# rgbstripe_msgeq7.net
KiCad netlist of a schematic drawn in EAGLE
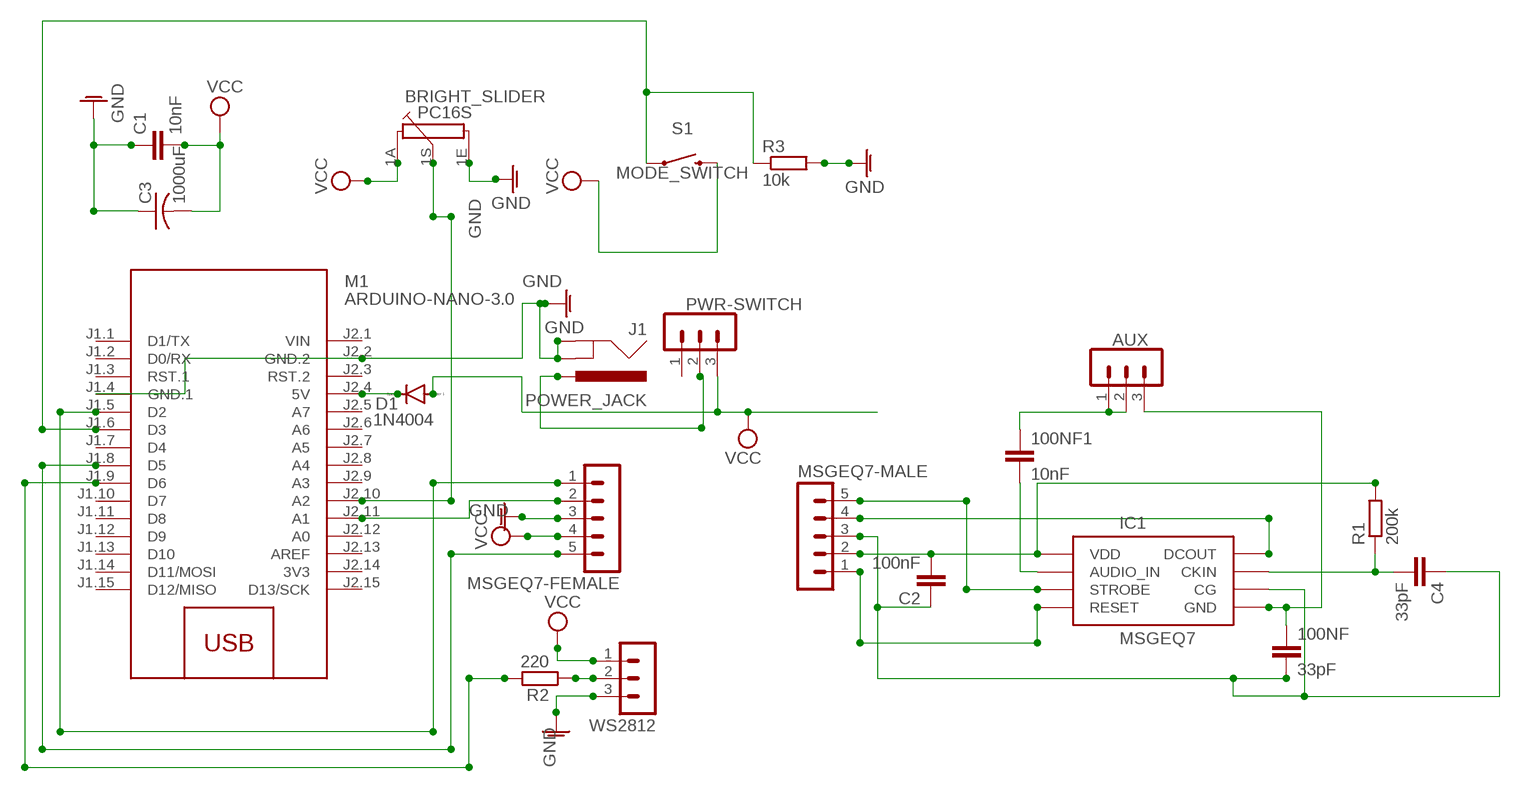
[diagram p0: schematic, sheet 1]

(export (version "E")
  (design (tool "Eeschema 10.0.6"))
  (components
    (comp (ref "100NF")
      (value "33pF")
      (footprint "eagle-import:C025-025X050")
      (libsource (lib "eagle-import") (part "C-EU025-025X050"))
    )
    (comp (ref "100NF1")
      (value "10nF")
      (footprint "eagle-import:C025-025X050")
      (libsource (lib "eagle-import") (part "C-EU025-025X050"))
    )
    (comp (ref "AUX")
      (value "MA03-1")
      (footprint "eagle-import:MA03-1")
      (libsource (lib "eagle-import") (part "MA03-1"))
    )
    (comp (ref "BRIGHT_SLIDER")
      (value "PC16S")
      (footprint "eagle-import:PC16S")
      (libsource (lib "eagle-import") (part "PC16S"))
    )
    (comp (ref "C1")
      (value "10nF")
      (footprint "eagle-import:C025-025X050")
      (libsource (lib "eagle-import") (part "C-EU025-025X050"))
    )
    (comp (ref "C2")
      (value "100nF")
      (footprint "eagle-import:C025-025X050")
      (libsource (lib "eagle-import") (part "C-EU025-025X050"))
    )
    (comp (ref "C3")
      (value "1000uF")
      (footprint "eagle-import:C050-024X044")
      (libsource (lib "eagle-import") (part "C-US050-024X044"))
    )
    (comp (ref "C4")
      (value "33pF")
      (footprint "eagle-import:C025-025X050")
      (libsource (lib "eagle-import") (part "C-EU025-025X050"))
    )
    (comp (ref "D1")
      (value "1N4004")
      (footprint "eagle-import:DO41-10")
      (libsource (lib "eagle-import") (part "1N4004"))
    )
    (comp (ref "IC1")
      (value "MSGEQ7P")
      (footprint "eagle-import:DIP08")
      (libsource (lib "eagle-import") (part "MSGEQ7DIL"))
    )
    (comp (ref "J1")
      (value "POWER_JACK")
      (footprint "eagle-import:POWER_JACK_PTH")
      (libsource (lib "eagle-import") (part "POWER_JACK"))
    )
    (comp (ref "M1")
      (value "ARDUINO-NANO-3.0")
      (footprint "eagle-import:ARDUINO-NANO-3.0")
      (libsource (lib "eagle-import") (part "ARDUINO-NANO-3.0"))
    )
    (comp (ref "MSGEQ7-FEMALE")
      (value "MA05-1")
      (footprint "eagle-import:MA05-1")
      (libsource (lib "eagle-import") (part "MA05-1"))
    )
    (comp (ref "MSGEQ7-MALE")
      (value "MA05-1")
      (footprint "eagle-import:MA05-1")
      (libsource (lib "eagle-import") (part "MA05-1"))
    )
    (comp (ref "PWR-SWITCH")
      (value "MA03-1")
      (footprint "eagle-import:MA03-1")
      (libsource (lib "eagle-import") (part "MA03-1"))
    )
    (comp (ref "R1")
      (value "200k")
      (footprint "eagle-import:0204_5")
      (libsource (lib "eagle-import") (part "R-EU_0204/5"))
    )
    (comp (ref "R2")
      (value "220")
      (footprint "eagle-import:0204_5")
      (libsource (lib "eagle-import") (part "R-EU_0204/5"))
    )
    (comp (ref "R3")
      (value "10k")
      (footprint "eagle-import:0204_5")
      (libsource (lib "eagle-import") (part "R-EU_0204/5"))
    )
    (comp (ref "S1")
      (value "MODE_SWITCH")
      (footprint "eagle-import:TACTILE_SWITCH_PTH_12MM")
      (libsource (lib "eagle-import") (part "MOMENTARY-SWITCH-SPST-PTH-12MM"))
    )
    (comp (ref "WS2812")
      (value "MA03-1")
      (footprint "eagle-import:MA03-1")
      (libsource (lib "eagle-import") (part "MA03-1"))
    )
  )
  (nets
    (net (code "1") (name "/3V3") (class "Default")
      (node (ref "M1") (pin "J2.14") (pinfunction "3V3_J2.14") (pintype "power_in"))
    )
    (net (code "2") (name "/VIN") (class "Default")
      (node (ref "M1") (pin "J2.1") (pinfunction "VIN_J2.1") (pintype "power_in"))
    )
    (net (code "3") (name "GND") (class "Default")
      (node (ref "BRIGHT_SLIDER") (pin "1E") (pinfunction "1E_1E") (pintype "passive"))
      (node (ref "C1") (pin "1") (pinfunction "1_1") (pintype "passive"))
      (node (ref "C3") (pin "1") (pinfunction "1_1") (pintype "passive"))
      (node (ref "J1") (pin "GND") (pinfunction "GND_GND") (pintype "bidirectional"))
      (node (ref "J1") (pin "GNDBREAK") (pinfunction "GNDBREAK_GNDBREAK") (pintype "bidirectional"))
      (node (ref "M1") (pin "J1.4") (pinfunction "GND.1_J1.4") (pintype "power_in"))
      (node (ref "M1") (pin "J2.2") (pinfunction "GND.2_J2.2") (pintype "power_in"))
      (node (ref "MSGEQ7-FEMALE") (pin "3") (pinfunction "3_3") (pintype "passive"))
      (node (ref "R3") (pin "2") (pinfunction "2_2") (pintype "passive"))
      (node (ref "WS2812") (pin "3") (pinfunction "3_3") (pintype "passive"))
    )
    (net (code "4") (name "Net-(100NF1-Pad1)") (class "Default")
      (node (ref "100NF1") (pin "1") (pinfunction "1_1") (pintype "passive"))
      (node (ref "AUX") (pin "1") (pinfunction "1_1") (pintype "passive"))
      (node (ref "AUX") (pin "2") (pinfunction "2_2") (pintype "passive"))
    )
    (net (code "5") (name "Net-(IC1-AUDIO_IN)") (class "Default")
      (node (ref "100NF1") (pin "2") (pinfunction "2_2") (pintype "passive"))
      (node (ref "IC1") (pin "5") (pinfunction "AUDIO_IN_5") (pintype "input"))
    )
    (net (code "6") (name "Net-(IC1-CG)") (class "Default")
      (node (ref "100NF") (pin "2") (pinfunction "2_2") (pintype "passive"))
      (node (ref "C2") (pin "1") (pinfunction "1_1") (pintype "passive"))
      (node (ref "C4") (pin "1") (pinfunction "1_1") (pintype "passive"))
      (node (ref "IC1") (pin "6") (pinfunction "CG_6") (pintype "bidirectional"))
      (node (ref "MSGEQ7-MALE") (pin "3") (pinfunction "3_3") (pintype "passive"))
    )
    (net (code "7") (name "Net-(IC1-CKIN)") (class "Default")
      (node (ref "C4") (pin "2") (pinfunction "2_2") (pintype "passive"))
      (node (ref "IC1") (pin "8") (pinfunction "CKIN_8") (pintype "bidirectional"))
      (node (ref "R1") (pin "1") (pinfunction "1_1") (pintype "passive"))
    )
    (net (code "8") (name "Net-(IC1-DCOUT)") (class "Default")
      (node (ref "IC1") (pin "3") (pinfunction "DCOUT_3") (pintype "bidirectional"))
      (node (ref "MSGEQ7-MALE") (pin "4") (pinfunction "4_4") (pintype "passive"))
    )
    (net (code "9") (name "Net-(IC1-GND)") (class "Default")
      (node (ref "100NF") (pin "1") (pinfunction "1_1") (pintype "passive"))
      (node (ref "AUX") (pin "3") (pinfunction "3_3") (pintype "passive"))
      (node (ref "IC1") (pin "2") (pinfunction "GND_2") (pintype "bidirectional"))
    )
    (net (code "10") (name "Net-(IC1-RESET)") (class "Default")
      (node (ref "IC1") (pin "7") (pinfunction "RESET_7") (pintype "input"))
      (node (ref "MSGEQ7-MALE") (pin "1") (pinfunction "1_1") (pintype "passive"))
    )
    (net (code "11") (name "Net-(IC1-STROBE)") (class "Default")
      (node (ref "IC1") (pin "4") (pinfunction "STROBE_4") (pintype "input"))
      (node (ref "MSGEQ7-MALE") (pin "5") (pinfunction "5_5") (pintype "passive"))
    )
    (net (code "12") (name "Net-(IC1-VDD)") (class "Default")
      (node (ref "C2") (pin "2") (pinfunction "2_2") (pintype "passive"))
      (node (ref "IC1") (pin "1") (pinfunction "VDD_1") (pintype "input"))
      (node (ref "MSGEQ7-MALE") (pin "2") (pinfunction "2_2") (pintype "passive"))
      (node (ref "R1") (pin "2") (pinfunction "2_2") (pintype "passive"))
    )
    (net (code "13") (name "Net-(J1-PadPWR)") (class "Default")
      (node (ref "J1") (pin "PWR") (pinfunction "PWR_PWR") (pintype "bidirectional"))
      (node (ref "PWR-SWITCH") (pin "2") (pinfunction "2_2") (pintype "passive"))
    )
    (net (code "14") (name "Net-(M1-5V)") (class "Default")
      (node (ref "D1") (pin "C") (pinfunction "C_C") (pintype "passive"))
      (node (ref "M1") (pin "J2.4") (pinfunction "5V_J2.4") (pintype "power_in"))
    )
    (net (code "15") (name "Net-(M1-A1)") (class "Default")
      (node (ref "M1") (pin "J2.11") (pinfunction "A1_J2.11") (pintype "bidirectional"))
      (node (ref "MSGEQ7-FEMALE") (pin "2") (pinfunction "2_2") (pintype "passive"))
    )
    (net (code "16") (name "Net-(M1-A2)") (class "Default")
      (node (ref "BRIGHT_SLIDER") (pin "1S") (pinfunction "1S_1S") (pintype "passive"))
      (node (ref "M1") (pin "J2.10") (pinfunction "A2_J2.10") (pintype "bidirectional"))
    )
    (net (code "17") (name "Net-(M1-D2)") (class "Default")
      (node (ref "M1") (pin "J1.5") (pinfunction "D2_J1.5") (pintype "bidirectional"))
      (node (ref "MSGEQ7-FEMALE") (pin "1") (pinfunction "1_1") (pintype "passive"))
    )
    (net (code "18") (name "Net-(M1-D3)") (class "Default")
      (node (ref "M1") (pin "J1.6") (pinfunction "D3_J1.6") (pintype "bidirectional"))
      (node (ref "R3") (pin "1") (pinfunction "1_1") (pintype "passive"))
      (node (ref "S1") (pin "1") (pinfunction "1_1") (pintype "passive"))
    )
    (net (code "19") (name "Net-(M1-D5)") (class "Default")
      (node (ref "M1") (pin "J1.8") (pinfunction "D5_J1.8") (pintype "bidirectional"))
      (node (ref "MSGEQ7-FEMALE") (pin "5") (pinfunction "5_5") (pintype "passive"))
    )
    (net (code "20") (name "Net-(M1-D6)") (class "Default")
      (node (ref "M1") (pin "J1.9") (pinfunction "D6_J1.9") (pintype "bidirectional"))
      (node (ref "R2") (pin "2") (pinfunction "2_2") (pintype "passive"))
    )
    (net (code "21") (name "Net-(R2-Pad1)") (class "Default")
      (node (ref "R2") (pin "1") (pinfunction "1_1") (pintype "passive"))
      (node (ref "WS2812") (pin "2") (pinfunction "2_2") (pintype "passive"))
    )
    (net (code "22") (name "VCC") (class "Default")
      (node (ref "BRIGHT_SLIDER") (pin "1A") (pinfunction "1A_1A") (pintype "passive"))
      (node (ref "C1") (pin "2") (pinfunction "2_2") (pintype "passive"))
      (node (ref "C3") (pin "2") (pinfunction "2_2") (pintype "passive"))
      (node (ref "D1") (pin "A") (pinfunction "A_A") (pintype "passive"))
      (node (ref "MSGEQ7-FEMALE") (pin "4") (pinfunction "4_4") (pintype "passive"))
      (node (ref "PWR-SWITCH") (pin "3") (pinfunction "3_3") (pintype "passive"))
      (node (ref "S1") (pin "3") (pinfunction "2_3") (pintype "passive"))
      (node (ref "WS2812") (pin "1") (pinfunction "1_1") (pintype "passive"))
    )
    (net (code "23") (name "unconnected-(M1-A0-PadJ2.12)") (class "Default")
      (node (ref "M1") (pin "J2.12") (pinfunction "A0_J2.12") (pintype "bidirectional"))
    )
    (net (code "24") (name "unconnected-(M1-A3-PadJ2.9)") (class "Default")
      (node (ref "M1") (pin "J2.9") (pinfunction "A3_J2.9") (pintype "bidirectional"))
    )
    (net (code "25") (name "unconnected-(M1-A4-PadJ2.8)") (class "Default")
      (node (ref "M1") (pin "J2.8") (pinfunction "A4_J2.8") (pintype "bidirectional"))
    )
    (net (code "26") (name "unconnected-(M1-A5-PadJ2.7)") (class "Default")
      (node (ref "M1") (pin "J2.7") (pinfunction "A5_J2.7") (pintype "bidirectional"))
    )
    (net (code "27") (name "unconnected-(M1-A6-PadJ2.6)") (class "Default")
      (node (ref "M1") (pin "J2.6") (pinfunction "A6_J2.6") (pintype "bidirectional"))
    )
    (net (code "28") (name "unconnected-(M1-A7-PadJ2.5)") (class "Default")
      (node (ref "M1") (pin "J2.5") (pinfunction "A7_J2.5") (pintype "bidirectional"))
    )
    (net (code "29") (name "unconnected-(M1-AREF-PadJ2.13)") (class "Default")
      (node (ref "M1") (pin "J2.13") (pinfunction "AREF_J2.13") (pintype "bidirectional"))
    )
    (net (code "30") (name "unconnected-(M1-D0{slash}RX-PadJ1.2)") (class "Default")
      (node (ref "M1") (pin "J1.2") (pinfunction "D0/RX_J1.2") (pintype "bidirectional"))
    )
    (net (code "31") (name "unconnected-(M1-D1{slash}TX-PadJ1.1)") (class "Default")
      (node (ref "M1") (pin "J1.1") (pinfunction "D1/TX_J1.1") (pintype "bidirectional"))
    )
    (net (code "32") (name "unconnected-(M1-D4-PadJ1.7)") (class "Default")
      (node (ref "M1") (pin "J1.7") (pinfunction "D4_J1.7") (pintype "bidirectional"))
    )
    (net (code "33") (name "unconnected-(M1-D7-PadJ1.10)") (class "Default")
      (node (ref "M1") (pin "J1.10") (pinfunction "D7_J1.10") (pintype "bidirectional"))
    )
    (net (code "34") (name "unconnected-(M1-D8-PadJ1.11)") (class "Default")
      (node (ref "M1") (pin "J1.11") (pinfunction "D8_J1.11") (pintype "bidirectional"))
    )
    (net (code "35") (name "unconnected-(M1-D9-PadJ1.12)") (class "Default")
      (node (ref "M1") (pin "J1.12") (pinfunction "D9_J1.12") (pintype "bidirectional"))
    )
    (net (code "36") (name "unconnected-(M1-D10-PadJ1.13)") (class "Default")
      (node (ref "M1") (pin "J1.13") (pinfunction "D10_J1.13") (pintype "bidirectional"))
    )
    (net (code "37") (name "unconnected-(M1-D11{slash}MOSI-PadJ1.14)") (class "Default")
      (node (ref "M1") (pin "J1.14") (pinfunction "D11/MOSI_J1.14") (pintype "bidirectional"))
    )
    (net (code "38") (name "unconnected-(M1-D12{slash}MISO-PadJ1.15)") (class "Default")
      (node (ref "M1") (pin "J1.15") (pinfunction "D12/MISO_J1.15") (pintype "bidirectional"))
    )
    (net (code "39") (name "unconnected-(M1-D13{slash}SCK-PadJ2.15)") (class "Default")
      (node (ref "M1") (pin "J2.15") (pinfunction "D13/SCK_J2.15") (pintype "bidirectional"))
    )
    (net (code "40") (name "unconnected-(M1-RST.1-PadJ1.3)") (class "Default")
      (node (ref "M1") (pin "J1.3") (pinfunction "RST.1_J1.3") (pintype "bidirectional"))
    )
    (net (code "41") (name "unconnected-(M1-RST.2-PadJ2.3)") (class "Default")
      (node (ref "M1") (pin "J2.3") (pinfunction "RST.2_J2.3") (pintype "bidirectional"))
    )
    (net (code "42") (name "unconnected-(PWR-SWITCH-Pad1)") (class "Default")
      (node (ref "PWR-SWITCH") (pin "1") (pinfunction "1_1") (pintype "passive"))
    )
  )
)
